# 450B679C.net
KiCad netlist of a schematic drawn in EAGLE
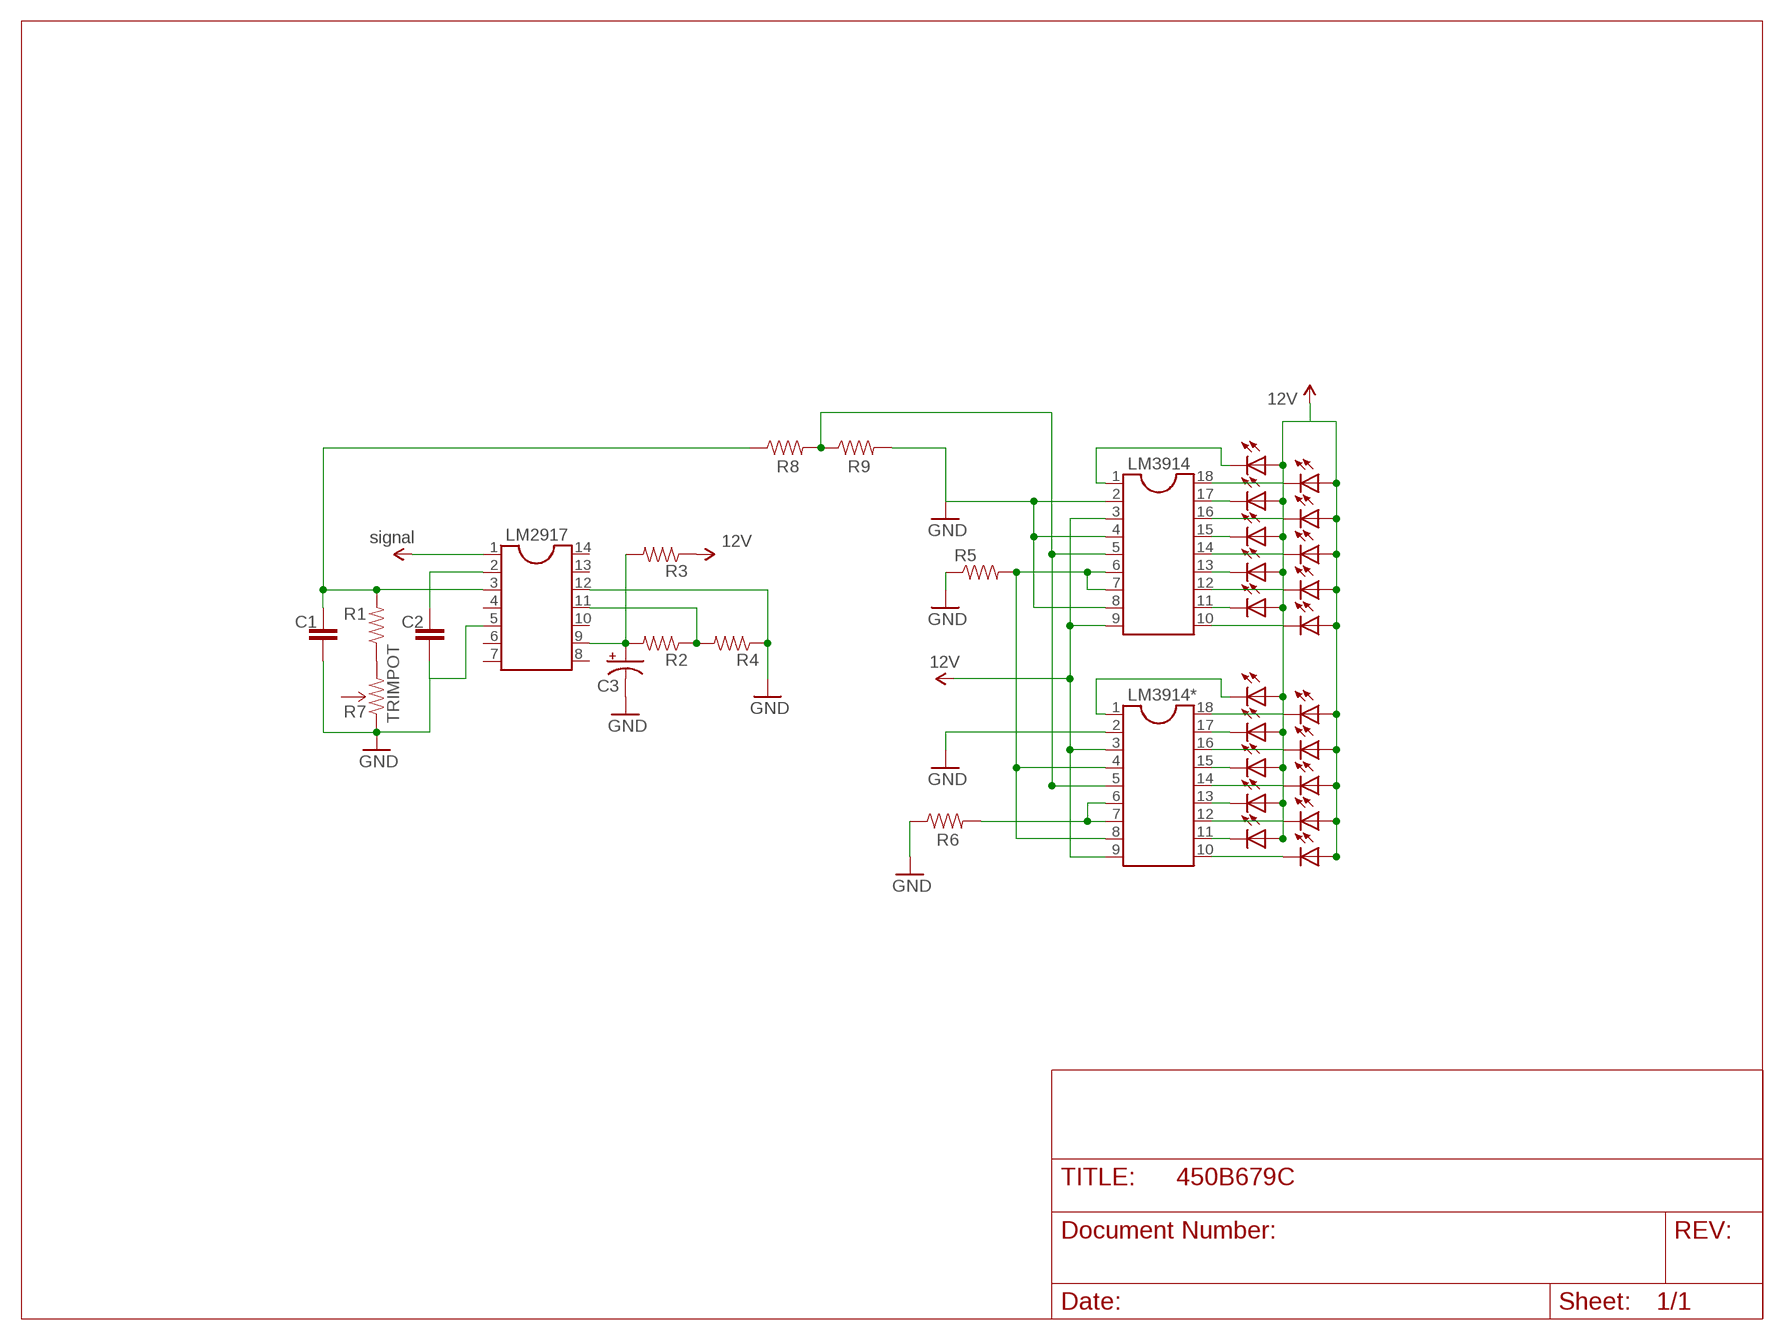
[diagram p0: schematic, sheet 1]

(export (version "E")
  (design (tool "Eeschema 10.0.6"))
  (components
    (comp (ref "C1")
      (value "CAPPTH1")
      (footprint "eagle-import:CAP-PTH-5MM")
      (libsource (lib "eagle-import") (part "CAPPTH1"))
    )
    (comp (ref "C2")
      (value "CAPPTH1")
      (footprint "eagle-import:CAP-PTH-5MM")
      (libsource (lib "eagle-import") (part "CAPPTH1"))
    )
    (comp (ref "C3")
      (value "CAP_POLPTH2")
      (footprint "eagle-import:CPOL-RADIAL-10UF-25V")
      (libsource (lib "eagle-import") (part "CAP_POLPTH2"))
    )
    (comp (ref "LED1")
      (value "LED5MM")
      (footprint "eagle-import:LED5MM")
      (libsource (lib "eagle-import") (part "LED5MM"))
    )
    (comp (ref "LED2")
      (value "LED5MM")
      (footprint "eagle-import:LED5MM")
      (libsource (lib "eagle-import") (part "LED5MM"))
    )
    (comp (ref "LED3")
      (value "LED5MM")
      (footprint "eagle-import:LED5MM")
      (libsource (lib "eagle-import") (part "LED5MM"))
    )
    (comp (ref "LED4")
      (value "LED5MM")
      (footprint "eagle-import:LED5MM")
      (libsource (lib "eagle-import") (part "LED5MM"))
    )
    (comp (ref "LED5")
      (value "LED5MM")
      (footprint "eagle-import:LED5MM")
      (libsource (lib "eagle-import") (part "LED5MM"))
    )
    (comp (ref "LED6")
      (value "LED5MM")
      (footprint "eagle-import:LED5MM")
      (libsource (lib "eagle-import") (part "LED5MM"))
    )
    (comp (ref "LED7")
      (value "LED5MM")
      (footprint "eagle-import:LED5MM")
      (libsource (lib "eagle-import") (part "LED5MM"))
    )
    (comp (ref "LED8")
      (value "LED5MM")
      (footprint "eagle-import:LED5MM")
      (libsource (lib "eagle-import") (part "LED5MM"))
    )
    (comp (ref "LED9")
      (value "LED5MM")
      (footprint "eagle-import:LED5MM")
      (libsource (lib "eagle-import") (part "LED5MM"))
    )
    (comp (ref "LED10")
      (value "LED5MM")
      (footprint "eagle-import:LED5MM")
      (libsource (lib "eagle-import") (part "LED5MM"))
    )
    (comp (ref "LED11")
      (value "LED5MM")
      (footprint "eagle-import:LED5MM")
      (libsource (lib "eagle-import") (part "LED5MM"))
    )
    (comp (ref "LED12")
      (value "LED5MM")
      (footprint "eagle-import:LED5MM")
      (libsource (lib "eagle-import") (part "LED5MM"))
    )
    (comp (ref "LED13")
      (value "LED5MM")
      (footprint "eagle-import:LED5MM")
      (libsource (lib "eagle-import") (part "LED5MM"))
    )
    (comp (ref "LED14")
      (value "LED5MM")
      (footprint "eagle-import:LED5MM")
      (libsource (lib "eagle-import") (part "LED5MM"))
    )
    (comp (ref "LED15")
      (value "LED5MM")
      (footprint "eagle-import:LED5MM")
      (libsource (lib "eagle-import") (part "LED5MM"))
    )
    (comp (ref "LED16")
      (value "LED5MM")
      (footprint "eagle-import:LED5MM")
      (libsource (lib "eagle-import") (part "LED5MM"))
    )
    (comp (ref "LED17")
      (value "LED5MM")
      (footprint "eagle-import:LED5MM")
      (libsource (lib "eagle-import") (part "LED5MM"))
    )
    (comp (ref "LED18")
      (value "LED5MM")
      (footprint "eagle-import:LED5MM")
      (libsource (lib "eagle-import") (part "LED5MM"))
    )
    (comp (ref "LED19")
      (value "LED5MM")
      (footprint "eagle-import:LED5MM")
      (libsource (lib "eagle-import") (part "LED5MM"))
    )
    (comp (ref "LED20")
      (value "LED5MM")
      (footprint "eagle-import:LED5MM")
      (libsource (lib "eagle-import") (part "LED5MM"))
    )
    (comp (ref "LM2917")
      (value "DIL14")
      (footprint "eagle-import:DIL14")
      (libsource (lib "eagle-import") (part "DIL14"))
    )
    (comp (ref "LM3914")
      (value "DIL18")
      (footprint "eagle-import:DIL18")
      (libsource (lib "eagle-import") (part "DIL18"))
    )
    (comp (ref "LM3914*")
      (value "DIL18")
      (footprint "eagle-import:DIL18")
      (libsource (lib "eagle-import") (part "DIL18"))
    )
    (comp (ref "R1")
      (value "RESISTORPTH-1/4W")
      (footprint "eagle-import:AXIAL-0.4")
      (libsource (lib "eagle-import") (part "RESISTORPTH-1/4W"))
    )
    (comp (ref "R2")
      (value "RESISTORPTH-1/4W")
      (footprint "eagle-import:AXIAL-0.4")
      (libsource (lib "eagle-import") (part "RESISTORPTH-1/4W"))
    )
    (comp (ref "R3")
      (value "RESISTORPTH-1/4W")
      (footprint "eagle-import:AXIAL-0.4")
      (libsource (lib "eagle-import") (part "RESISTORPTH-1/4W"))
    )
    (comp (ref "R4")
      (value "RESISTORPTH-1/4W")
      (footprint "eagle-import:AXIAL-0.4")
      (libsource (lib "eagle-import") (part "RESISTORPTH-1/4W"))
    )
    (comp (ref "R5")
      (value "RESISTORPTH-1/4W")
      (footprint "eagle-import:AXIAL-0.4")
      (libsource (lib "eagle-import") (part "RESISTORPTH-1/4W"))
    )
    (comp (ref "R6")
      (value "RESISTORPTH-1/4W")
      (footprint "eagle-import:AXIAL-0.4")
      (libsource (lib "eagle-import") (part "RESISTORPTH-1/4W"))
    )
    (comp (ref "R7")
      (value "TRIMPOT")
      (footprint "eagle-import:3362U-2")
      (libsource (lib "eagle-import") (part "TRIMPOT"))
    )
    (comp (ref "R8")
      (value "RESISTORPTH-1/4W")
      (footprint "eagle-import:AXIAL-0.4")
      (libsource (lib "eagle-import") (part "RESISTORPTH-1/4W"))
    )
    (comp (ref "R9")
      (value "RESISTORPTH-1/4W")
      (footprint "eagle-import:AXIAL-0.4")
      (libsource (lib "eagle-import") (part "RESISTORPTH-1/4W"))
    )
  )
  (nets
    (net (code "1") (name "12V") (class "Default")
      (node (ref "LED1") (pin "A") (pinfunction "A_A") (pintype "passive"))
      (node (ref "LED10") (pin "A") (pinfunction "A_A") (pintype "passive"))
      (node (ref "LED11") (pin "A") (pinfunction "A_A") (pintype "passive"))
      (node (ref "LED12") (pin "A") (pinfunction "A_A") (pintype "passive"))
      (node (ref "LED13") (pin "A") (pinfunction "A_A") (pintype "passive"))
      (node (ref "LED14") (pin "A") (pinfunction "A_A") (pintype "passive"))
      (node (ref "LED15") (pin "A") (pinfunction "A_A") (pintype "passive"))
      (node (ref "LED16") (pin "A") (pinfunction "A_A") (pintype "passive"))
      (node (ref "LED17") (pin "A") (pinfunction "A_A") (pintype "passive"))
      (node (ref "LED18") (pin "A") (pinfunction "A_A") (pintype "passive"))
      (node (ref "LED19") (pin "A") (pinfunction "A_A") (pintype "passive"))
      (node (ref "LED2") (pin "A") (pinfunction "A_A") (pintype "passive"))
      (node (ref "LED20") (pin "A") (pinfunction "A_A") (pintype "passive"))
      (node (ref "LED3") (pin "A") (pinfunction "A_A") (pintype "passive"))
      (node (ref "LED4") (pin "A") (pinfunction "A_A") (pintype "passive"))
      (node (ref "LED5") (pin "A") (pinfunction "A_A") (pintype "passive"))
      (node (ref "LED6") (pin "A") (pinfunction "A_A") (pintype "passive"))
      (node (ref "LED7") (pin "A") (pinfunction "A_A") (pintype "passive"))
      (node (ref "LED8") (pin "A") (pinfunction "A_A") (pintype "passive"))
      (node (ref "LED9") (pin "A") (pinfunction "A_A") (pintype "passive"))
      (node (ref "LM2917") (pin "1") (pinfunction "1_1") (pintype "passive"))
      (node (ref "LM3914") (pin "3") (pinfunction "3_3") (pintype "passive"))
      (node (ref "LM3914") (pin "9") (pinfunction "9_9") (pintype "passive"))
      (node (ref "LM3914*") (pin "3") (pinfunction "3_3") (pintype "passive"))
      (node (ref "LM3914*") (pin "9") (pinfunction "9_9") (pintype "passive"))
      (node (ref "R3") (pin "P$1") (pinfunction "1_P$1") (pintype "passive"))
    )
    (net (code "2") (name "GND") (class "Default")
      (node (ref "C1") (pin "1") (pinfunction "1_1") (pintype "passive"))
      (node (ref "C2") (pin "1") (pinfunction "1_1") (pintype "passive"))
      (node (ref "C3") (pin "2") (pinfunction "-_2") (pintype "passive"))
      (node (ref "LM2917") (pin "12") (pinfunction "12_12") (pintype "passive"))
      (node (ref "LM2917") (pin "5") (pinfunction "5_5") (pintype "passive"))
      (node (ref "LM3914") (pin "2") (pinfunction "2_2") (pintype "passive"))
      (node (ref "LM3914") (pin "4") (pinfunction "4_4") (pintype "passive"))
      (node (ref "LM3914") (pin "8") (pinfunction "8_8") (pintype "passive"))
      (node (ref "LM3914*") (pin "2") (pinfunction "2_2") (pintype "passive"))
      (node (ref "R4") (pin "P$1") (pinfunction "1_P$1") (pintype "passive"))
      (node (ref "R5") (pin "P$1") (pinfunction "1_P$1") (pintype "passive"))
      (node (ref "R6") (pin "P$1") (pinfunction "1_P$1") (pintype "passive"))
      (node (ref "R7") (pin "1") (pinfunction "CCW_1") (pintype "passive"))
      (node (ref "R9") (pin "P$2") (pinfunction "2_P$2") (pintype "passive"))
    )
    (net (code "3") (name "Net-(C2-Pad2)") (class "Default")
      (node (ref "C2") (pin "2") (pinfunction "2_2") (pintype "passive"))
      (node (ref "LM2917") (pin "2") (pinfunction "2_2") (pintype "passive"))
    )
    (net (code "4") (name "Net-(C3-+)") (class "Default")
      (node (ref "C3") (pin "1") (pinfunction "+_1") (pintype "passive"))
      (node (ref "LM2917") (pin "9") (pinfunction "9_9") (pintype "passive"))
      (node (ref "R2") (pin "P$2") (pinfunction "2_P$2") (pintype "passive"))
      (node (ref "R3") (pin "P$2") (pinfunction "2_P$2") (pintype "passive"))
    )
    (net (code "5") (name "Net-(LED1-C)") (class "Default")
      (node (ref "LED1") (pin "K") (pinfunction "C_K") (pintype "passive"))
      (node (ref "LM3914") (pin "1") (pinfunction "1_1") (pintype "passive"))
    )
    (net (code "6") (name "Net-(LED2-C)") (class "Default")
      (node (ref "LED2") (pin "K") (pinfunction "C_K") (pintype "passive"))
      (node (ref "LM3914") (pin "18") (pinfunction "18_18") (pintype "passive"))
    )
    (net (code "7") (name "Net-(LED3-C)") (class "Default")
      (node (ref "LED3") (pin "K") (pinfunction "C_K") (pintype "passive"))
      (node (ref "LM3914") (pin "16") (pinfunction "16_16") (pintype "passive"))
    )
    (net (code "8") (name "Net-(LED4-C)") (class "Default")
      (node (ref "LED4") (pin "K") (pinfunction "C_K") (pintype "passive"))
      (node (ref "LM3914") (pin "17") (pinfunction "17_17") (pintype "passive"))
    )
    (net (code "9") (name "Net-(LED5-C)") (class "Default")
      (node (ref "LED5") (pin "K") (pinfunction "C_K") (pintype "passive"))
      (node (ref "LM3914") (pin "15") (pinfunction "15_15") (pintype "passive"))
    )
    (net (code "10") (name "Net-(LED6-C)") (class "Default")
      (node (ref "LED6") (pin "K") (pinfunction "C_K") (pintype "passive"))
      (node (ref "LM3914") (pin "14") (pinfunction "14_14") (pintype "passive"))
    )
    (net (code "11") (name "Net-(LED7-C)") (class "Default")
      (node (ref "LED7") (pin "K") (pinfunction "C_K") (pintype "passive"))
      (node (ref "LM3914") (pin "13") (pinfunction "13_13") (pintype "passive"))
    )
    (net (code "12") (name "Net-(LED8-C)") (class "Default")
      (node (ref "LED8") (pin "K") (pinfunction "C_K") (pintype "passive"))
      (node (ref "LM3914") (pin "12") (pinfunction "12_12") (pintype "passive"))
    )
    (net (code "13") (name "Net-(LED9-C)") (class "Default")
      (node (ref "LED9") (pin "K") (pinfunction "C_K") (pintype "passive"))
      (node (ref "LM3914") (pin "10") (pinfunction "10_10") (pintype "passive"))
    )
    (net (code "14") (name "Net-(LED10-C)") (class "Default")
      (node (ref "LED10") (pin "K") (pinfunction "C_K") (pintype "passive"))
      (node (ref "LM3914") (pin "11") (pinfunction "11_11") (pintype "passive"))
    )
    (net (code "15") (name "Net-(LED11-C)") (class "Default")
      (node (ref "LED11") (pin "K") (pinfunction "C_K") (pintype "passive"))
      (node (ref "LM3914*") (pin "1") (pinfunction "1_1") (pintype "passive"))
    )
    (net (code "16") (name "Net-(LED12-C)") (class "Default")
      (node (ref "LED12") (pin "K") (pinfunction "C_K") (pintype "passive"))
      (node (ref "LM3914*") (pin "18") (pinfunction "18_18") (pintype "passive"))
    )
    (net (code "17") (name "Net-(LED13-C)") (class "Default")
      (node (ref "LED13") (pin "K") (pinfunction "C_K") (pintype "passive"))
      (node (ref "LM3914*") (pin "15") (pinfunction "15_15") (pintype "passive"))
    )
    (net (code "18") (name "Net-(LED14-C)") (class "Default")
      (node (ref "LED14") (pin "K") (pinfunction "C_K") (pintype "passive"))
      (node (ref "LM3914*") (pin "13") (pinfunction "13_13") (pintype "passive"))
    )
    (net (code "19") (name "Net-(LED15-C)") (class "Default")
      (node (ref "LED15") (pin "K") (pinfunction "C_K") (pintype "passive"))
      (node (ref "LM3914*") (pin "12") (pinfunction "12_12") (pintype "passive"))
    )
    (net (code "20") (name "Net-(LED16-C)") (class "Default")
      (node (ref "LED16") (pin "K") (pinfunction "C_K") (pintype "passive"))
      (node (ref "LM3914*") (pin "10") (pinfunction "10_10") (pintype "passive"))
    )
    (net (code "21") (name "Net-(LED17-C)") (class "Default")
      (node (ref "LED17") (pin "K") (pinfunction "C_K") (pintype "passive"))
      (node (ref "LM3914*") (pin "16") (pinfunction "16_16") (pintype "passive"))
    )
    (net (code "22") (name "Net-(LED18-C)") (class "Default")
      (node (ref "LED18") (pin "K") (pinfunction "C_K") (pintype "passive"))
      (node (ref "LM3914*") (pin "17") (pinfunction "17_17") (pintype "passive"))
    )
    (net (code "23") (name "Net-(LED19-C)") (class "Default")
      (node (ref "LED19") (pin "K") (pinfunction "C_K") (pintype "passive"))
      (node (ref "LM3914*") (pin "11") (pinfunction "11_11") (pintype "passive"))
    )
    (net (code "24") (name "Net-(LED20-C)") (class "Default")
      (node (ref "LED20") (pin "K") (pinfunction "C_K") (pintype "passive"))
      (node (ref "LM3914*") (pin "14") (pinfunction "14_14") (pintype "passive"))
    )
    (net (code "25") (name "Net-(R1-1)") (class "Default")
      (node (ref "R1") (pin "P$1") (pinfunction "1_P$1") (pintype "passive"))
      (node (ref "R7") (pin "3") (pinfunction "CW_3") (pintype "passive"))
    )
    (net (code "26") (name "Net-(R1-2)") (class "Default")
      (node (ref "C1") (pin "2") (pinfunction "2_2") (pintype "passive"))
      (node (ref "LM2917") (pin "3") (pinfunction "3_3") (pintype "passive"))
      (node (ref "R1") (pin "P$2") (pinfunction "2_P$2") (pintype "passive"))
      (node (ref "R8") (pin "P$1") (pinfunction "1_P$1") (pintype "passive"))
    )
    (net (code "27") (name "Net-(R2-1)") (class "Default")
      (node (ref "LM2917") (pin "11") (pinfunction "11_11") (pintype "passive"))
      (node (ref "R2") (pin "P$1") (pinfunction "1_P$1") (pintype "passive"))
      (node (ref "R4") (pin "P$2") (pinfunction "2_P$2") (pintype "passive"))
    )
    (net (code "28") (name "Net-(R5-2)") (class "Default")
      (node (ref "LM3914") (pin "6") (pinfunction "6_6") (pintype "passive"))
      (node (ref "LM3914") (pin "7") (pinfunction "7_7") (pintype "passive"))
      (node (ref "LM3914*") (pin "4") (pinfunction "4_4") (pintype "passive"))
      (node (ref "LM3914*") (pin "8") (pinfunction "8_8") (pintype "passive"))
      (node (ref "R5") (pin "P$2") (pinfunction "2_P$2") (pintype "passive"))
    )
    (net (code "29") (name "Net-(R6-2)") (class "Default")
      (node (ref "LM3914*") (pin "6") (pinfunction "6_6") (pintype "passive"))
      (node (ref "LM3914*") (pin "7") (pinfunction "7_7") (pintype "passive"))
      (node (ref "R6") (pin "P$2") (pinfunction "2_P$2") (pintype "passive"))
    )
    (net (code "30") (name "Net-(R8-2)") (class "Default")
      (node (ref "LM3914") (pin "5") (pinfunction "5_5") (pintype "passive"))
      (node (ref "LM3914*") (pin "5") (pinfunction "5_5") (pintype "passive"))
      (node (ref "R8") (pin "P$2") (pinfunction "2_P$2") (pintype "passive"))
      (node (ref "R9") (pin "P$1") (pinfunction "1_P$1") (pintype "passive"))
    )
    (net (code "31") (name "unconnected-(LM2917-Pad4)") (class "Default")
      (node (ref "LM2917") (pin "4") (pinfunction "4_4") (pintype "passive"))
    )
    (net (code "32") (name "unconnected-(LM2917-Pad6)") (class "Default")
      (node (ref "LM2917") (pin "6") (pinfunction "6_6") (pintype "passive"))
    )
    (net (code "33") (name "unconnected-(LM2917-Pad7)") (class "Default")
      (node (ref "LM2917") (pin "7") (pinfunction "7_7") (pintype "passive"))
    )
    (net (code "34") (name "unconnected-(LM2917-Pad8)") (class "Default")
      (node (ref "LM2917") (pin "8") (pinfunction "8_8") (pintype "passive"))
    )
    (net (code "35") (name "unconnected-(LM2917-Pad10)") (class "Default")
      (node (ref "LM2917") (pin "10") (pinfunction "10_10") (pintype "passive"))
    )
    (net (code "36") (name "unconnected-(LM2917-Pad13)") (class "Default")
      (node (ref "LM2917") (pin "13") (pinfunction "13_13") (pintype "passive"))
    )
    (net (code "37") (name "unconnected-(LM2917-Pad14)") (class "Default")
      (node (ref "LM2917") (pin "14") (pinfunction "14_14") (pintype "passive"))
    )
    (net (code "38") (name "unconnected-(R7-WIPER-Pad2)") (class "Default")
      (node (ref "R7") (pin "2") (pinfunction "WIPER_2") (pintype "passive"))
    )
  )
)
